# nufsr-fsr.net
KiCad netlist of a schematic drawn in Altium Designer
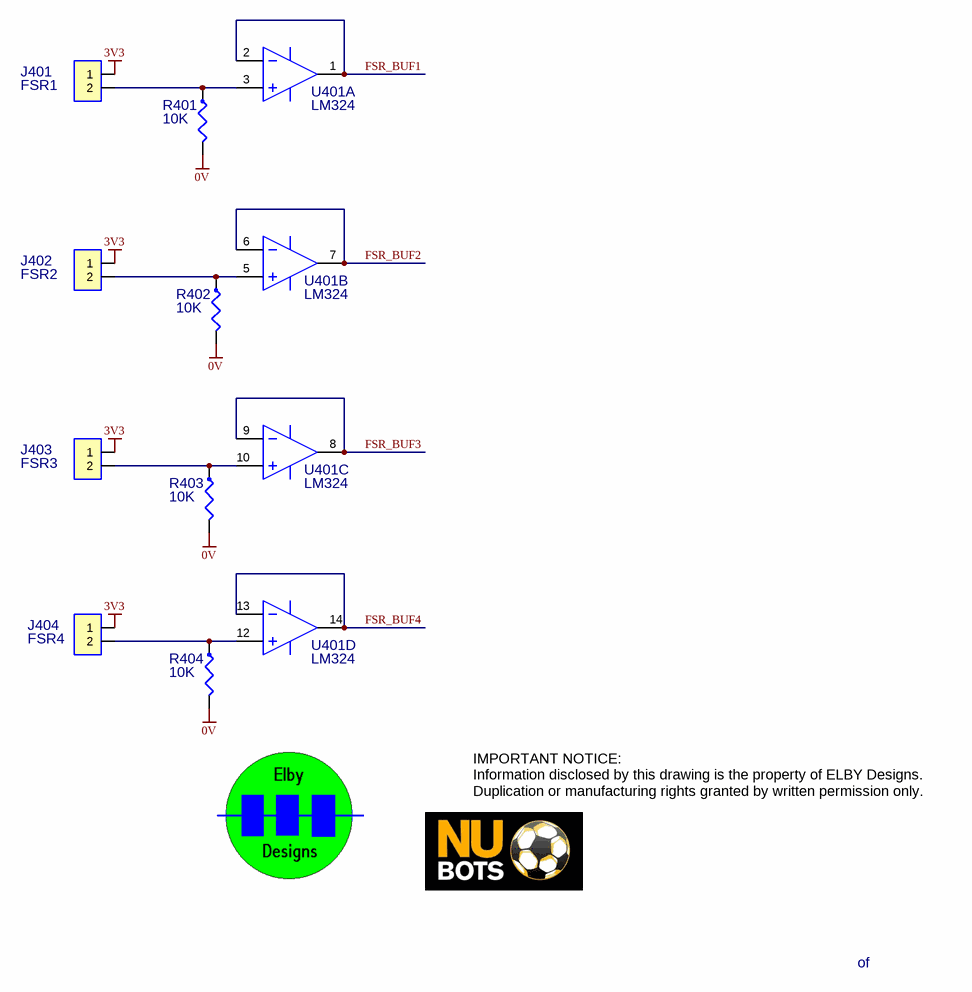
[diagram p0: nufsr-fsr.schdoc]

(export (version "E")
  (design (tool "Eeschema 10.0.6"))
  (components
    (comp (ref "J401")
      (value "FSR1")
      (footprint "JST-B2B-PH")
      (libsource (lib "connectors") (part "CON2(LB)"))
    )
    (comp (ref "J402")
      (value "FSR2")
      (footprint "JST-B2B-PH")
      (libsource (lib "connectors") (part "CON2(LB)"))
    )
    (comp (ref "J403")
      (value "FSR3")
      (footprint "JST-B2B-PH")
      (libsource (lib "connectors") (part "CON2(LB)"))
    )
    (comp (ref "J404")
      (value "FSR4")
      (footprint "JST-B2B-PH")
      (libsource (lib "connectors") (part "CON2(LB)"))
    )
    (comp (ref "R401")
      (value "10K")
      (footprint "0603(LB)")
      (description "0.5W 1% Metal Film Resistor")
      (libsource (lib "resistor") (part "RM-10K(LB)"))
    )
    (comp (ref "R402")
      (value "10K")
      (footprint "0603(LB)")
      (description "0.5W 1% Metal Film Resistor")
      (libsource (lib "resistor") (part "RM-10K(LB)"))
    )
    (comp (ref "R403")
      (value "10K")
      (footprint "0603(LB)")
      (description "0.5W 1% Metal Film Resistor")
      (libsource (lib "resistor") (part "RM-10K(LB)"))
    )
    (comp (ref "R404")
      (value "10K")
      (footprint "0603(LB)")
      (description "0.5W 1% Metal Film Resistor")
      (libsource (lib "resistor") (part "RM-10K(LB)"))
    )
    (comp (ref "U401")
      (value "LM324")
      (description "Quad Low-noise JFET Op-amp")
      (libsource (lib "ic") (part "LM324(LB)"))
    )
  )
  (nets
    (net (code "1") (name "/FSR_BUF1") (class "Default")
      (node (ref "U401") (pin "1") (pinfunction "OUT_1") (pintype "passive"))
      (node (ref "U401") (pin "2") (pinfunction "IN1-_2") (pintype "passive"))
    )
    (net (code "2") (name "/FSR_BUF2") (class "Default")
      (node (ref "U401") (pin "6") (pinfunction "IN2-_6") (pintype "passive"))
      (node (ref "U401") (pin "7") (pinfunction "OUT_7") (pintype "passive"))
    )
    (net (code "3") (name "/FSR_BUF3") (class "Default")
      (node (ref "U401") (pin "8") (pinfunction "OUT_8") (pintype "passive"))
      (node (ref "U401") (pin "9") (pinfunction "IN3-_9") (pintype "passive"))
    )
    (net (code "4") (name "/FSR_BUF4") (class "Default")
      (node (ref "U401") (pin "13") (pinfunction "IN4-_13") (pintype "passive"))
      (node (ref "U401") (pin "14") (pinfunction "OUT_14") (pintype "passive"))
    )
    (net (code "5") (name "0V") (class "Default")
      (node (ref "R401") (pin "2") (pinfunction "2_2") (pintype "passive"))
      (node (ref "R402") (pin "2") (pinfunction "2_2") (pintype "passive"))
      (node (ref "R403") (pin "2") (pinfunction "2_2") (pintype "passive"))
      (node (ref "R404") (pin "2") (pinfunction "2_2") (pintype "passive"))
    )
    (net (code "6") (name "3V3") (class "Default")
      (node (ref "J401") (pin "1") (pinfunction "1_1") (pintype "passive"))
      (node (ref "J402") (pin "1") (pinfunction "1_1") (pintype "passive"))
      (node (ref "J403") (pin "1") (pinfunction "1_1") (pintype "passive"))
      (node (ref "J404") (pin "1") (pinfunction "1_1") (pintype "passive"))
    )
    (net (code "7") (name "Net-(U401A-IN1+)") (class "Default")
      (node (ref "J401") (pin "2") (pinfunction "2_2") (pintype "passive"))
      (node (ref "R401") (pin "1") (pinfunction "1_1") (pintype "passive"))
      (node (ref "U401") (pin "3") (pinfunction "IN1+_3") (pintype "passive"))
    )
    (net (code "8") (name "Net-(U401B-IN2+)") (class "Default")
      (node (ref "J402") (pin "2") (pinfunction "2_2") (pintype "passive"))
      (node (ref "R402") (pin "1") (pinfunction "1_1") (pintype "passive"))
      (node (ref "U401") (pin "5") (pinfunction "IN2+_5") (pintype "passive"))
    )
    (net (code "9") (name "Net-(U401C-IN3+)") (class "Default")
      (node (ref "J403") (pin "2") (pinfunction "2_2") (pintype "passive"))
      (node (ref "R403") (pin "1") (pinfunction "1_1") (pintype "passive"))
      (node (ref "U401") (pin "10") (pinfunction "IN3+_10") (pintype "passive"))
    )
    (net (code "10") (name "Net-(U401D-IN4+)") (class "Default")
      (node (ref "J404") (pin "2") (pinfunction "2_2") (pintype "passive"))
      (node (ref "R404") (pin "1") (pinfunction "1_1") (pintype "passive"))
      (node (ref "U401") (pin "12") (pinfunction "IN4+_12") (pintype "passive"))
    )
  )
)
